# untitled_2_mask.net
KiCad netlist of a schematic drawn in EAGLE
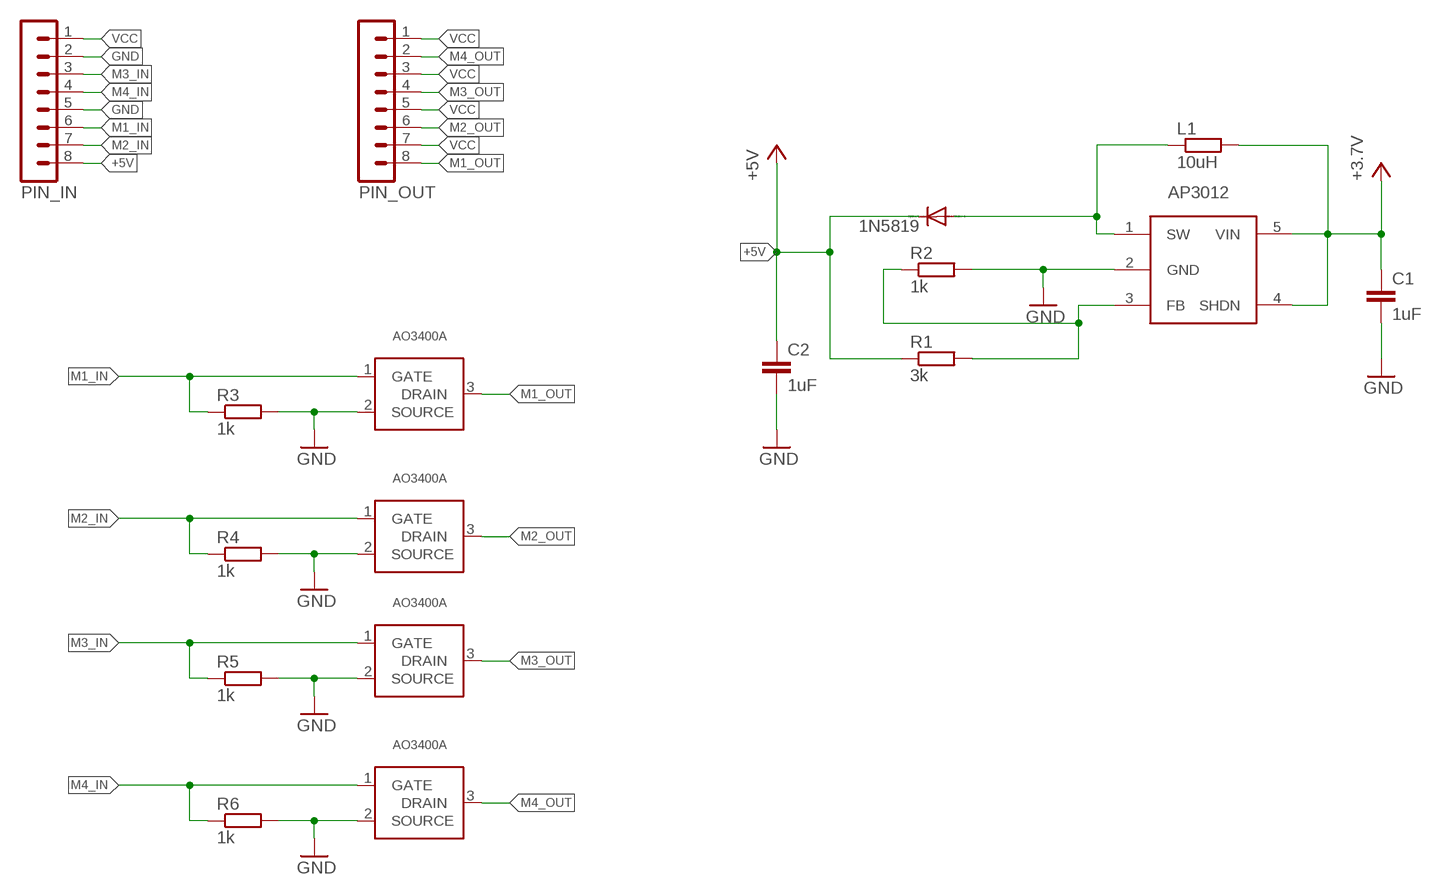
[diagram p0: schematic, sheet 1]

(export (version "E")
  (design (tool "Eeschema 10.0.6"))
  (components
    (comp (ref "1N5819")
      (value "DIODE-DO214AC")
      (footprint "eagle-import:DO214AC")
      (libsource (lib "eagle-import") (part "DIODE-DO214AC"))
    )
    (comp (ref "C1")
      (value "1uF")
      (footprint "eagle-import:C1206")
      (libsource (lib "eagle-import") (part "C-EUC1206"))
    )
    (comp (ref "C2")
      (value "1uF")
      (footprint "eagle-import:C1206")
      (libsource (lib "eagle-import") (part "C-EUC1206"))
    )
    (comp (ref "L1")
      (value "10uH")
      (footprint "eagle-import:R0805")
      (libsource (lib "eagle-import") (part "R-EU_R0805"))
    )
    (comp (ref "MOSFET1")
      (value "AO3400A")
      (footprint "eagle-import:SOT-23")
      (libsource (lib "eagle-import") (part "AO3400A"))
    )
    (comp (ref "MOSFET2")
      (value "AO3400A")
      (footprint "eagle-import:SOT-23")
      (libsource (lib "eagle-import") (part "AO3400A"))
    )
    (comp (ref "MOSFET3")
      (value "AO3400A")
      (footprint "eagle-import:SOT-23")
      (libsource (lib "eagle-import") (part "AO3400A"))
    )
    (comp (ref "MOSFET4")
      (value "AO3400A")
      (footprint "eagle-import:SOT-23")
      (libsource (lib "eagle-import") (part "AO3400A"))
    )
    (comp (ref "PIN_IN")
      (value "MA08-1")
      (footprint "eagle-import:MA08-1")
      (libsource (lib "eagle-import") (part "MA08-1"))
    )
    (comp (ref "PIN_OUT")
      (value "MA08-1")
      (footprint "eagle-import:MA08-1")
      (libsource (lib "eagle-import") (part "MA08-1"))
    )
    (comp (ref "R1")
      (value "3k")
      (footprint "eagle-import:R1206")
      (libsource (lib "eagle-import") (part "R-EU_R1206"))
    )
    (comp (ref "R2")
      (value "1k")
      (footprint "eagle-import:R1206")
      (libsource (lib "eagle-import") (part "R-EU_R1206"))
    )
    (comp (ref "R3")
      (value "1k")
      (footprint "eagle-import:R1206")
      (libsource (lib "eagle-import") (part "R-EU_R1206"))
    )
    (comp (ref "R4")
      (value "1k")
      (footprint "eagle-import:R1206")
      (libsource (lib "eagle-import") (part "R-EU_R1206"))
    )
    (comp (ref "R5")
      (value "1k")
      (footprint "eagle-import:R1206")
      (libsource (lib "eagle-import") (part "R-EU_R1206"))
    )
    (comp (ref "R6")
      (value "1k")
      (footprint "eagle-import:R1206")
      (libsource (lib "eagle-import") (part "R-EU_R1206"))
    )
    (comp (ref "U$1")
      (value "AP3012")
      (footprint "eagle-import:SOT-23-5")
      (libsource (lib "eagle-import") (part "AP3012"))
    )
  )
  (nets
    (net (code "1") (name "+5V") (class "Default")
      (node (ref "1N5819") (pin "C") (pinfunction "C_C") (pintype "passive"))
      (node (ref "C2") (pin "1") (pinfunction "1_1") (pintype "passive"))
      (node (ref "PIN_IN") (pin "8") (pinfunction "8_8") (pintype "passive"))
      (node (ref "R1") (pin "1") (pinfunction "1_1") (pintype "passive"))
    )
    (net (code "2") (name "GND") (class "Default")
      (node (ref "C1") (pin "2") (pinfunction "2_2") (pintype "passive"))
      (node (ref "C2") (pin "2") (pinfunction "2_2") (pintype "passive"))
      (node (ref "MOSFET1") (pin "2") (pinfunction "SOURCE_2") (pintype "bidirectional"))
      (node (ref "MOSFET2") (pin "2") (pinfunction "SOURCE_2") (pintype "bidirectional"))
      (node (ref "MOSFET3") (pin "2") (pinfunction "SOURCE_2") (pintype "bidirectional"))
      (node (ref "MOSFET4") (pin "2") (pinfunction "SOURCE_2") (pintype "bidirectional"))
      (node (ref "PIN_IN") (pin "2") (pinfunction "2_2") (pintype "passive"))
      (node (ref "PIN_IN") (pin "5") (pinfunction "5_5") (pintype "passive"))
      (node (ref "R2") (pin "2") (pinfunction "2_2") (pintype "passive"))
      (node (ref "R3") (pin "2") (pinfunction "2_2") (pintype "passive"))
      (node (ref "R4") (pin "2") (pinfunction "2_2") (pintype "passive"))
      (node (ref "R5") (pin "2") (pinfunction "2_2") (pintype "passive"))
      (node (ref "R6") (pin "2") (pinfunction "2_2") (pintype "passive"))
      (node (ref "U$1") (pin "2") (pinfunction "GND_2") (pintype "bidirectional"))
    )
    (net (code "3") (name "M1_IN") (class "Default")
      (node (ref "MOSFET1") (pin "1") (pinfunction "GATE_1") (pintype "bidirectional"))
      (node (ref "PIN_IN") (pin "6") (pinfunction "6_6") (pintype "passive"))
      (node (ref "R3") (pin "1") (pinfunction "1_1") (pintype "passive"))
    )
    (net (code "4") (name "M1_OUT") (class "Default")
      (node (ref "MOSFET1") (pin "3") (pinfunction "DRAIN_3") (pintype "bidirectional"))
      (node (ref "PIN_OUT") (pin "8") (pinfunction "8_8") (pintype "passive"))
    )
    (net (code "5") (name "M2_IN") (class "Default")
      (node (ref "MOSFET2") (pin "1") (pinfunction "GATE_1") (pintype "bidirectional"))
      (node (ref "PIN_IN") (pin "7") (pinfunction "7_7") (pintype "passive"))
      (node (ref "R4") (pin "1") (pinfunction "1_1") (pintype "passive"))
    )
    (net (code "6") (name "M2_OUT") (class "Default")
      (node (ref "MOSFET2") (pin "3") (pinfunction "DRAIN_3") (pintype "bidirectional"))
      (node (ref "PIN_OUT") (pin "6") (pinfunction "6_6") (pintype "passive"))
    )
    (net (code "7") (name "M3_IN") (class "Default")
      (node (ref "MOSFET3") (pin "1") (pinfunction "GATE_1") (pintype "bidirectional"))
      (node (ref "PIN_IN") (pin "3") (pinfunction "3_3") (pintype "passive"))
      (node (ref "R5") (pin "1") (pinfunction "1_1") (pintype "passive"))
    )
    (net (code "8") (name "M3_OUT") (class "Default")
      (node (ref "MOSFET3") (pin "3") (pinfunction "DRAIN_3") (pintype "bidirectional"))
      (node (ref "PIN_OUT") (pin "4") (pinfunction "4_4") (pintype "passive"))
    )
    (net (code "9") (name "M4_IN") (class "Default")
      (node (ref "MOSFET4") (pin "1") (pinfunction "GATE_1") (pintype "bidirectional"))
      (node (ref "PIN_IN") (pin "4") (pinfunction "4_4") (pintype "passive"))
      (node (ref "R6") (pin "1") (pinfunction "1_1") (pintype "passive"))
    )
    (net (code "10") (name "M4_OUT") (class "Default")
      (node (ref "MOSFET4") (pin "3") (pinfunction "DRAIN_3") (pintype "bidirectional"))
      (node (ref "PIN_OUT") (pin "2") (pinfunction "2_2") (pintype "passive"))
    )
    (net (code "11") (name "Net-(U$1-FB)") (class "Default")
      (node (ref "R1") (pin "2") (pinfunction "2_2") (pintype "passive"))
      (node (ref "R2") (pin "1") (pinfunction "1_1") (pintype "passive"))
      (node (ref "U$1") (pin "3") (pinfunction "FB_3") (pintype "bidirectional"))
    )
    (net (code "12") (name "Net-(U$1-SW)") (class "Default")
      (node (ref "1N5819") (pin "A") (pinfunction "A_A") (pintype "passive"))
      (node (ref "L1") (pin "1") (pinfunction "1_1") (pintype "passive"))
      (node (ref "U$1") (pin "1") (pinfunction "SW_1") (pintype "bidirectional"))
    )
    (net (code "13") (name "VCC") (class "Default")
      (node (ref "C1") (pin "1") (pinfunction "1_1") (pintype "passive"))
      (node (ref "L1") (pin "2") (pinfunction "2_2") (pintype "passive"))
      (node (ref "PIN_IN") (pin "1") (pinfunction "1_1") (pintype "passive"))
      (node (ref "PIN_OUT") (pin "1") (pinfunction "1_1") (pintype "passive"))
      (node (ref "PIN_OUT") (pin "3") (pinfunction "3_3") (pintype "passive"))
      (node (ref "PIN_OUT") (pin "5") (pinfunction "5_5") (pintype "passive"))
      (node (ref "PIN_OUT") (pin "7") (pinfunction "7_7") (pintype "passive"))
      (node (ref "U$1") (pin "4") (pinfunction "SHDN_4") (pintype "bidirectional"))
      (node (ref "U$1") (pin "5") (pinfunction "VIN_5") (pintype "bidirectional"))
    )
  )
)
